# main.net
KiCad netlist of a schematic drawn in EAGLE
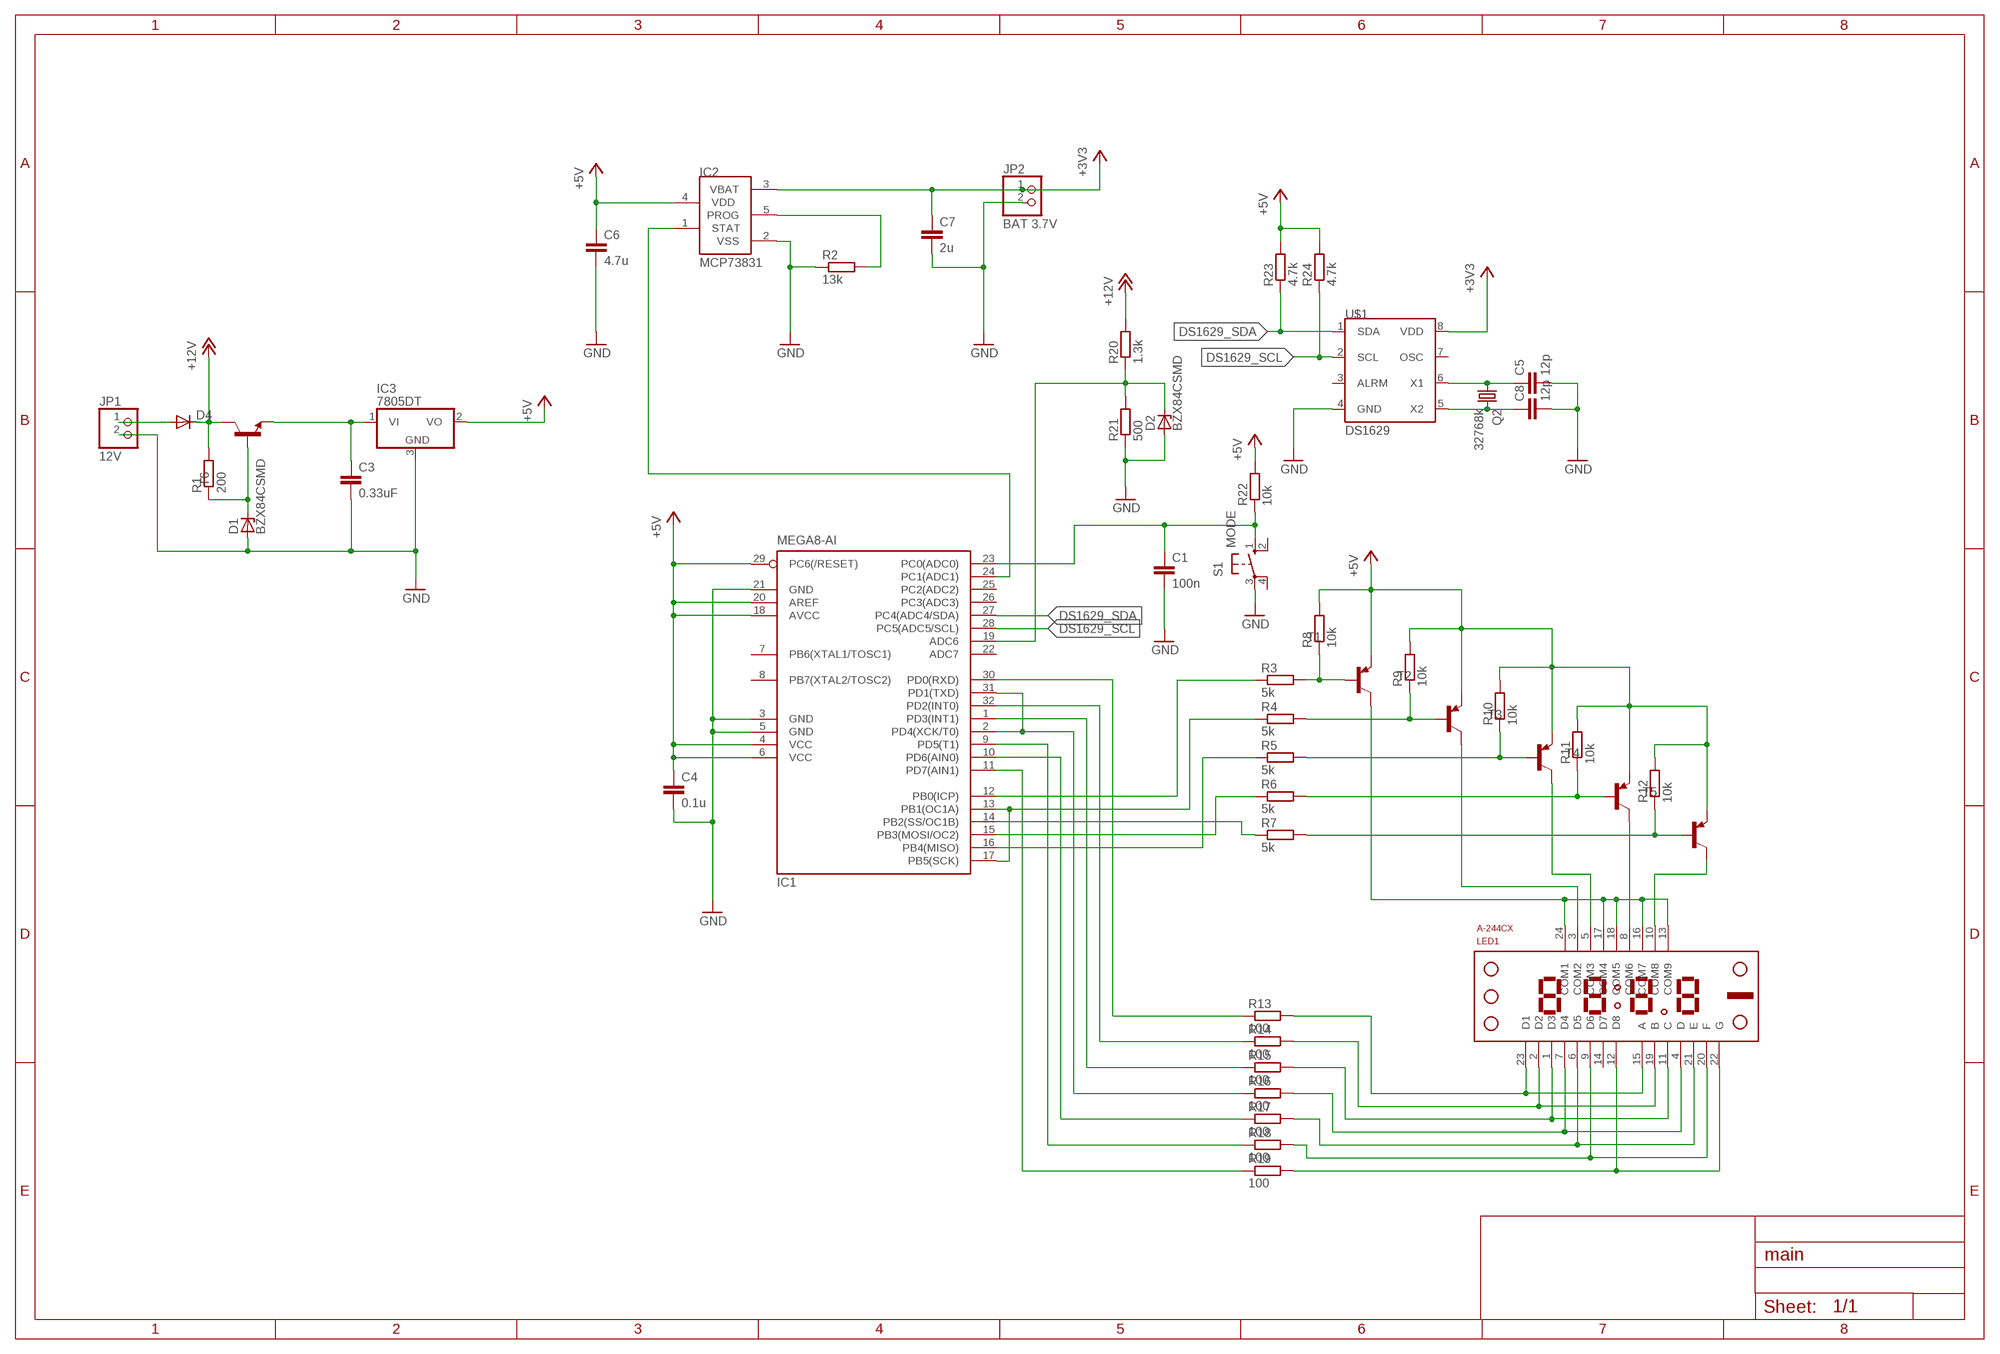
[diagram p0: schematic, sheet 1]

(export (version "E")
  (design (tool "Eeschema 10.0.6"))
  (components
    (comp (ref "C1")
      (value "100n")
      (footprint "eagle-import:C0805")
      (libsource (lib "eagle-import") (part "C-EUC0805"))
    )
    (comp (ref "C3")
      (value "0.33uF")
      (footprint "eagle-import:C1206")
      (libsource (lib "eagle-import") (part "C-EUC1206"))
    )
    (comp (ref "C4")
      (value "0.1u")
      (footprint "eagle-import:C0805")
      (libsource (lib "eagle-import") (part "C-EUC0805"))
    )
    (comp (ref "C5")
      (value "12p")
      (footprint "eagle-import:C0805")
      (libsource (lib "eagle-import") (part "C-EUC0805"))
    )
    (comp (ref "C6")
      (value "4.7u")
      (footprint "eagle-import:C1206")
      (libsource (lib "eagle-import") (part "C-EUC1206"))
    )
    (comp (ref "C7")
      (value "2u")
      (footprint "eagle-import:C1206")
      (libsource (lib "eagle-import") (part "C-EUC1206"))
    )
    (comp (ref "C8")
      (value "12p")
      (footprint "eagle-import:C0805")
      (libsource (lib "eagle-import") (part "C-EUC0805"))
    )
    (comp (ref "D1")
      (value "BZX84CSMD")
      (footprint "eagle-import:TO236")
      (libsource (lib "eagle-import") (part "BZX84CSMD"))
    )
    (comp (ref "D2")
      (value "BZX84CSMD")
      (footprint "eagle-import:TO236")
      (libsource (lib "eagle-import") (part "BZX84CSMD"))
    )
    (comp (ref "D4")
      (value "DIODE-D-7.5")
      (footprint "eagle-import:D-7.5")
      (libsource (lib "eagle-import") (part "DIODE-D-7.5"))
    )
    (comp (ref "IC1")
      (value "MEGA8-AI")
      (footprint "eagle-import:TQFP32-08")
      (fields (field (name "MPN") "ATMEGA8-16AU"))
      (libsource (lib "eagle-import") (part "MEGA8-AI"))
    )
    (comp (ref "IC2")
      (value "MCP73831")
      (footprint "eagle-import:SOT23-5L")
      (libsource (lib "eagle-import") (part "MCP73831"))
    )
    (comp (ref "IC3")
      (value "7805DT")
      (footprint "eagle-import:TO252")
      (libsource (lib "eagle-import") (part "78DT05"))
    )
    (comp (ref "JP1")
      (value "12V")
      (footprint "eagle-import:1X02")
      (libsource (lib "eagle-import") (part "PINHD-1X2"))
    )
    (comp (ref "JP2")
      (value "BAT 3.7V")
      (footprint "eagle-import:1X02")
      (libsource (lib "eagle-import") (part "PINHD-1X2"))
    )
    (comp (ref "LED1")
      (value "A-244CX")
      (footprint "eagle-import:C_A-244CX")
      (libsource (lib "eagle-import") (part "A-244CX"))
    )
    (comp (ref "Q2")
      (value "32768k")
      (footprint "eagle-import:TC26H")
      (libsource (lib "eagle-import") (part "CRYSTALTC26H"))
    )
    (comp (ref "R1")
      (value "200")
      (footprint "eagle-import:M0805")
      (libsource (lib "eagle-import") (part "R-EU_M0805"))
    )
    (comp (ref "R2")
      (value "13k")
      (footprint "eagle-import:M0805")
      (libsource (lib "eagle-import") (part "R-EU_M0805"))
    )
    (comp (ref "R3")
      (value "5k")
      (footprint "eagle-import:M0805")
      (libsource (lib "eagle-import") (part "R-EU_M0805"))
    )
    (comp (ref "R4")
      (value "5k")
      (footprint "eagle-import:M0805")
      (libsource (lib "eagle-import") (part "R-EU_M0805"))
    )
    (comp (ref "R5")
      (value "5k")
      (footprint "eagle-import:M0805")
      (libsource (lib "eagle-import") (part "R-EU_M0805"))
    )
    (comp (ref "R6")
      (value "5k")
      (footprint "eagle-import:M0805")
      (libsource (lib "eagle-import") (part "R-EU_M0805"))
    )
    (comp (ref "R7")
      (value "5k")
      (footprint "eagle-import:M0805")
      (libsource (lib "eagle-import") (part "R-EU_M0805"))
    )
    (comp (ref "R8")
      (value "10k")
      (footprint "eagle-import:M0805")
      (libsource (lib "eagle-import") (part "R-EU_M0805"))
    )
    (comp (ref "R9")
      (value "10k")
      (footprint "eagle-import:M0805")
      (libsource (lib "eagle-import") (part "R-EU_M0805"))
    )
    (comp (ref "R10")
      (value "10k")
      (footprint "eagle-import:M0805")
      (libsource (lib "eagle-import") (part "R-EU_M0805"))
    )
    (comp (ref "R11")
      (value "10k")
      (footprint "eagle-import:M0805")
      (libsource (lib "eagle-import") (part "R-EU_M0805"))
    )
    (comp (ref "R12")
      (value "10k")
      (footprint "eagle-import:M0805")
      (libsource (lib "eagle-import") (part "R-EU_M0805"))
    )
    (comp (ref "R13")
      (value "100")
      (footprint "eagle-import:M0805")
      (libsource (lib "eagle-import") (part "R-EU_M0805"))
    )
    (comp (ref "R14")
      (value "100")
      (footprint "eagle-import:M0805")
      (libsource (lib "eagle-import") (part "R-EU_M0805"))
    )
    (comp (ref "R15")
      (value "100")
      (footprint "eagle-import:M0805")
      (libsource (lib "eagle-import") (part "R-EU_M0805"))
    )
    (comp (ref "R16")
      (value "100")
      (footprint "eagle-import:M0805")
      (libsource (lib "eagle-import") (part "R-EU_M0805"))
    )
    (comp (ref "R17")
      (value "100")
      (footprint "eagle-import:M0805")
      (libsource (lib "eagle-import") (part "R-EU_M0805"))
    )
    (comp (ref "R18")
      (value "100")
      (footprint "eagle-import:M0805")
      (libsource (lib "eagle-import") (part "R-EU_M0805"))
    )
    (comp (ref "R19")
      (value "100")
      (footprint "eagle-import:M0805")
      (libsource (lib "eagle-import") (part "R-EU_M0805"))
    )
    (comp (ref "R20")
      (value "1.3k")
      (footprint "eagle-import:M0805")
      (libsource (lib "eagle-import") (part "R-EU_M0805"))
    )
    (comp (ref "R21")
      (value "500")
      (footprint "eagle-import:M0805")
      (libsource (lib "eagle-import") (part "R-EU_M0805"))
    )
    (comp (ref "R22")
      (value "10k")
      (footprint "eagle-import:M0805")
      (libsource (lib "eagle-import") (part "R-EU_M0805"))
    )
    (comp (ref "R23")
      (value "4.7k")
      (footprint "eagle-import:M0805")
      (libsource (lib "eagle-import") (part "R-EU_M0805"))
    )
    (comp (ref "R24")
      (value "4.7k")
      (footprint "eagle-import:M0805")
      (libsource (lib "eagle-import") (part "R-EU_M0805"))
    )
    (comp (ref "S1")
      (value "MODE")
      (footprint "eagle-import:B3F-10XX")
      (fields (field (name "MPN") "B3F-1000"))
      (libsource (lib "eagle-import") (part "10-XX"))
    )
    (comp (ref "T1")
      (value "BC807-25-PNP-SOT23-BEC")
      (footprint "eagle-import:SOT23-BEC")
      (libsource (lib "eagle-import") (part "-PNP-SOT23-BECBC807-25"))
    )
    (comp (ref "T2")
      (value "BC807-25-PNP-SOT23-BEC")
      (footprint "eagle-import:SOT23-BEC")
      (libsource (lib "eagle-import") (part "-PNP-SOT23-BECBC807-25"))
    )
    (comp (ref "T3")
      (value "BC807-25-PNP-SOT23-BEC")
      (footprint "eagle-import:SOT23-BEC")
      (libsource (lib "eagle-import") (part "-PNP-SOT23-BECBC807-25"))
    )
    (comp (ref "T4")
      (value "BC807-25-PNP-SOT23-BEC")
      (footprint "eagle-import:SOT23-BEC")
      (libsource (lib "eagle-import") (part "-PNP-SOT23-BECBC807-25"))
    )
    (comp (ref "T5")
      (value "BC807-25-PNP-SOT23-BEC")
      (footprint "eagle-import:SOT23-BEC")
      (libsource (lib "eagle-import") (part "-PNP-SOT23-BECBC807-25"))
    )
    (comp (ref "T6")
      (value "-NPN-SOT23-EBC")
      (footprint "eagle-import:SOT23-EBC")
      (libsource (lib "eagle-import") (part "-NPN-SOT23-EBC"))
    )
    (comp (ref "U$1")
      (value "DS1629")
      (footprint "eagle-import:SOIC-8")
      (libsource (lib "eagle-import") (part "DS1629"))
    )
  )
  (nets
    (net (code "1") (name "+3V3") (class "Default")
      (node (ref "C7") (pin "1") (pinfunction "1_1") (pintype "passive"))
      (node (ref "IC2") (pin "3") (pinfunction "VBAT_3") (pintype "bidirectional"))
      (node (ref "JP2") (pin "1") (pinfunction "1_1") (pintype "passive"))
      (node (ref "U$1") (pin "8") (pinfunction "VDD_8") (pintype "power_in"))
    )
    (net (code "2") (name "+5V") (class "Default")
      (node (ref "C4") (pin "1") (pinfunction "1_1") (pintype "passive"))
      (node (ref "C6") (pin "1") (pinfunction "1_1") (pintype "passive"))
      (node (ref "IC1") (pin "18") (pinfunction "AVCC_18") (pintype "power_in"))
      (node (ref "IC1") (pin "20") (pinfunction "AREF_20") (pintype "passive"))
      (node (ref "IC1") (pin "29") (pinfunction "PC6(/RESET)_29") (pintype "bidirectional"))
      (node (ref "IC1") (pin "4") (pinfunction "VCC_4") (pintype "power_in"))
      (node (ref "IC1") (pin "6") (pinfunction "VCC_6") (pintype "power_in"))
      (node (ref "IC2") (pin "4") (pinfunction "VDD_4") (pintype "bidirectional"))
      (node (ref "IC3") (pin "2") (pinfunction "VO_2") (pintype "passive"))
      (node (ref "R10") (pin "2") (pinfunction "2_2") (pintype "passive"))
      (node (ref "R11") (pin "2") (pinfunction "2_2") (pintype "passive"))
      (node (ref "R12") (pin "2") (pinfunction "2_2") (pintype "passive"))
      (node (ref "R22") (pin "2") (pinfunction "2_2") (pintype "passive"))
      (node (ref "R23") (pin "2") (pinfunction "2_2") (pintype "passive"))
      (node (ref "R24") (pin "2") (pinfunction "2_2") (pintype "passive"))
      (node (ref "R8") (pin "2") (pinfunction "2_2") (pintype "passive"))
      (node (ref "R9") (pin "2") (pinfunction "2_2") (pintype "passive"))
      (node (ref "T1") (pin "E") (pinfunction "E_E") (pintype "passive"))
      (node (ref "T2") (pin "E") (pinfunction "E_E") (pintype "passive"))
      (node (ref "T3") (pin "E") (pinfunction "E_E") (pintype "passive"))
      (node (ref "T4") (pin "E") (pinfunction "E_E") (pintype "passive"))
      (node (ref "T5") (pin "E") (pinfunction "E_E") (pintype "passive"))
    )
    (net (code "3") (name "+12V") (class "Default")
      (node (ref "D4") (pin "C") (pinfunction "C_C") (pintype "passive"))
      (node (ref "R1") (pin "2") (pinfunction "2_2") (pintype "passive"))
      (node (ref "R20") (pin "2") (pinfunction "2_2") (pintype "passive"))
      (node (ref "T6") (pin "C") (pinfunction "C_C") (pintype "passive"))
    )
    (net (code "4") (name "DS1629_SCL") (class "Default")
      (node (ref "IC1") (pin "28") (pinfunction "PC5(ADC5/SCL)_28") (pintype "bidirectional"))
      (node (ref "R24") (pin "1") (pinfunction "1_1") (pintype "passive"))
      (node (ref "U$1") (pin "2") (pinfunction "SCL_2") (pintype "input"))
    )
    (net (code "5") (name "DS1629_SDA") (class "Default")
      (node (ref "IC1") (pin "27") (pinfunction "PC4(ADC4/SDA)_27") (pintype "bidirectional"))
      (node (ref "R23") (pin "1") (pinfunction "1_1") (pintype "passive"))
      (node (ref "U$1") (pin "1") (pinfunction "SDA_1") (pintype "bidirectional"))
    )
    (net (code "6") (name "GND") (class "Default")
      (node (ref "C1") (pin "2") (pinfunction "2_2") (pintype "passive"))
      (node (ref "C3") (pin "2") (pinfunction "2_2") (pintype "passive"))
      (node (ref "C4") (pin "2") (pinfunction "2_2") (pintype "passive"))
      (node (ref "C5") (pin "2") (pinfunction "2_2") (pintype "passive"))
      (node (ref "C6") (pin "2") (pinfunction "2_2") (pintype "passive"))
      (node (ref "C7") (pin "2") (pinfunction "2_2") (pintype "passive"))
      (node (ref "C8") (pin "2") (pinfunction "2_2") (pintype "passive"))
      (node (ref "D1") (pin "A") (pinfunction "A_A") (pintype "passive"))
      (node (ref "D2") (pin "A") (pinfunction "A_A") (pintype "passive"))
      (node (ref "IC1") (pin "21") (pinfunction "GND_21") (pintype "power_in"))
      (node (ref "IC1") (pin "3") (pinfunction "GND_3") (pintype "power_in"))
      (node (ref "IC1") (pin "5") (pinfunction "GND_5") (pintype "power_in"))
      (node (ref "IC2") (pin "2") (pinfunction "VSS_2") (pintype "bidirectional"))
      (node (ref "IC3") (pin "3") (pinfunction "GND_3") (pintype "passive"))
      (node (ref "JP1") (pin "2") (pinfunction "2_2") (pintype "passive"))
      (node (ref "JP2") (pin "2") (pinfunction "2_2") (pintype "passive"))
      (node (ref "R2") (pin "1") (pinfunction "1_1") (pintype "passive"))
      (node (ref "R21") (pin "1") (pinfunction "1_1") (pintype "passive"))
      (node (ref "S1") (pin "3") (pinfunction "P_3") (pintype "passive"))
      (node (ref "U$1") (pin "4") (pinfunction "GND_4") (pintype "power_in"))
    )
    (net (code "7") (name "Net-(D1-PadC)") (class "Default")
      (node (ref "D1") (pin "C") (pinfunction "C_C") (pintype "passive"))
      (node (ref "R1") (pin "1") (pinfunction "1_1") (pintype "passive"))
      (node (ref "T6") (pin "B") (pinfunction "B_B") (pintype "passive"))
    )
    (net (code "8") (name "Net-(D4-PadA)") (class "Default")
      (node (ref "D4") (pin "A") (pinfunction "A_A") (pintype "passive"))
      (node (ref "JP1") (pin "1") (pinfunction "1_1") (pintype "passive"))
    )
    (net (code "9") (name "Net-(IC1-ADC6)") (class "Default")
      (node (ref "D2") (pin "C") (pinfunction "C_C") (pintype "passive"))
      (node (ref "IC1") (pin "19") (pinfunction "ADC6_19") (pintype "bidirectional"))
      (node (ref "R20") (pin "1") (pinfunction "1_1") (pintype "passive"))
      (node (ref "R21") (pin "2") (pinfunction "2_2") (pintype "passive"))
    )
    (net (code "10") (name "Net-(IC1-PB0(ICP))") (class "Default")
      (node (ref "IC1") (pin "12") (pinfunction "PB0(ICP)_12") (pintype "bidirectional"))
      (node (ref "R3") (pin "1") (pinfunction "1_1") (pintype "passive"))
    )
    (net (code "11") (name "Net-(IC1-PB1(OC1A))") (class "Default")
      (node (ref "IC1") (pin "13") (pinfunction "PB1(OC1A)_13") (pintype "bidirectional"))
      (node (ref "IC1") (pin "17") (pinfunction "PB5(SCK)_17") (pintype "bidirectional"))
      (node (ref "R4") (pin "1") (pinfunction "1_1") (pintype "passive"))
    )
    (net (code "12") (name "Net-(IC1-PB2(SS{slash}OC1B))") (class "Default")
      (node (ref "IC1") (pin "14") (pinfunction "PB2(SS/OC1B)_14") (pintype "bidirectional"))
      (node (ref "R7") (pin "1") (pinfunction "1_1") (pintype "passive"))
    )
    (net (code "13") (name "Net-(IC1-PB3(MOSI{slash}OC2))") (class "Default")
      (node (ref "IC1") (pin "15") (pinfunction "PB3(MOSI/OC2)_15") (pintype "bidirectional"))
      (node (ref "R6") (pin "1") (pinfunction "1_1") (pintype "passive"))
    )
    (net (code "14") (name "Net-(IC1-PB4(MISO))") (class "Default")
      (node (ref "IC1") (pin "16") (pinfunction "PB4(MISO)_16") (pintype "bidirectional"))
      (node (ref "R5") (pin "1") (pinfunction "1_1") (pintype "passive"))
    )
    (net (code "15") (name "Net-(IC1-PC0(ADC0))") (class "Default")
      (node (ref "C1") (pin "1") (pinfunction "1_1") (pintype "passive"))
      (node (ref "IC1") (pin "23") (pinfunction "PC0(ADC0)_23") (pintype "bidirectional"))
      (node (ref "R22") (pin "1") (pinfunction "1_1") (pintype "passive"))
      (node (ref "S1") (pin "1") (pinfunction "S_1") (pintype "passive"))
    )
    (net (code "16") (name "Net-(IC1-PC1(ADC1))") (class "Default")
      (node (ref "IC1") (pin "24") (pinfunction "PC1(ADC1)_24") (pintype "bidirectional"))
      (node (ref "IC2") (pin "1") (pinfunction "STAT_1") (pintype "bidirectional"))
    )
    (net (code "17") (name "Net-(IC1-PD0(RXD))") (class "Default")
      (node (ref "IC1") (pin "30") (pinfunction "PD0(RXD)_30") (pintype "bidirectional"))
      (node (ref "R13") (pin "1") (pinfunction "1_1") (pintype "passive"))
    )
    (net (code "18") (name "Net-(IC1-PD1(TXD))") (class "Default")
      (node (ref "IC1") (pin "2") (pinfunction "PD4(XCK/T0)_2") (pintype "bidirectional"))
      (node (ref "IC1") (pin "31") (pinfunction "PD1(TXD)_31") (pintype "bidirectional"))
      (node (ref "R16") (pin "1") (pinfunction "1_1") (pintype "passive"))
    )
    (net (code "19") (name "Net-(IC1-PD2(INT0))") (class "Default")
      (node (ref "IC1") (pin "32") (pinfunction "PD2(INT0)_32") (pintype "bidirectional"))
      (node (ref "R14") (pin "1") (pinfunction "1_1") (pintype "passive"))
    )
    (net (code "20") (name "Net-(IC1-PD3(INT1))") (class "Default")
      (node (ref "IC1") (pin "1") (pinfunction "PD3(INT1)_1") (pintype "bidirectional"))
      (node (ref "R15") (pin "1") (pinfunction "1_1") (pintype "passive"))
    )
    (net (code "21") (name "Net-(IC1-PD5(T1))") (class "Default")
      (node (ref "IC1") (pin "9") (pinfunction "PD5(T1)_9") (pintype "bidirectional"))
      (node (ref "R18") (pin "1") (pinfunction "1_1") (pintype "passive"))
    )
    (net (code "22") (name "Net-(IC1-PD6(AIN0))") (class "Default")
      (node (ref "IC1") (pin "10") (pinfunction "PD6(AIN0)_10") (pintype "bidirectional"))
      (node (ref "R17") (pin "1") (pinfunction "1_1") (pintype "passive"))
    )
    (net (code "23") (name "Net-(IC1-PD7(AIN1))") (class "Default")
      (node (ref "IC1") (pin "11") (pinfunction "PD7(AIN1)_11") (pintype "bidirectional"))
      (node (ref "R19") (pin "1") (pinfunction "1_1") (pintype "passive"))
    )
    (net (code "24") (name "Net-(IC2-PROG)") (class "Default")
      (node (ref "IC2") (pin "5") (pinfunction "PROG_5") (pintype "bidirectional"))
      (node (ref "R2") (pin "2") (pinfunction "2_2") (pintype "passive"))
    )
    (net (code "25") (name "Net-(IC3-VI)") (class "Default")
      (node (ref "C3") (pin "1") (pinfunction "1_1") (pintype "passive"))
      (node (ref "IC3") (pin "1") (pinfunction "VI_1") (pintype "input"))
      (node (ref "T6") (pin "E") (pinfunction "E_E") (pintype "passive"))
    )
    (net (code "26") (name "Net-(LED1-A)") (class "Default")
      (node (ref "LED1") (pin "15") (pinfunction "A_15") (pintype "bidirectional"))
      (node (ref "LED1") (pin "23") (pinfunction "D1_23") (pintype "bidirectional"))
      (node (ref "R13") (pin "2") (pinfunction "2_2") (pintype "passive"))
    )
    (net (code "27") (name "Net-(LED1-B)") (class "Default")
      (node (ref "LED1") (pin "19") (pinfunction "B_19") (pintype "bidirectional"))
      (node (ref "LED1") (pin "2") (pinfunction "D2_2") (pintype "bidirectional"))
      (node (ref "R14") (pin "2") (pinfunction "2_2") (pintype "passive"))
    )
    (net (code "28") (name "Net-(LED1-C)") (class "Default")
      (node (ref "LED1") (pin "1") (pinfunction "D3_1") (pintype "bidirectional"))
      (node (ref "LED1") (pin "11") (pinfunction "C_11") (pintype "bidirectional"))
      (node (ref "R15") (pin "2") (pinfunction "2_2") (pintype "passive"))
    )
    (net (code "29") (name "Net-(LED1-COM1)") (class "Default")
      (node (ref "LED1") (pin "13") (pinfunction "COM9_13") (pintype "bidirectional"))
      (node (ref "LED1") (pin "16") (pinfunction "COM7_16") (pintype "bidirectional"))
      (node (ref "LED1") (pin "17") (pinfunction "COM4_17") (pintype "bidirectional"))
      (node (ref "LED1") (pin "18") (pinfunction "COM5_18") (pintype "bidirectional"))
      (node (ref "LED1") (pin "24") (pinfunction "COM1_24") (pintype "bidirectional"))
      (node (ref "T1") (pin "C") (pinfunction "C_C") (pintype "passive"))
    )
    (net (code "30") (name "Net-(LED1-COM2)") (class "Default")
      (node (ref "LED1") (pin "3") (pinfunction "COM2_3") (pintype "bidirectional"))
      (node (ref "T2") (pin "C") (pinfunction "C_C") (pintype "passive"))
    )
    (net (code "31") (name "Net-(LED1-COM3)") (class "Default")
      (node (ref "LED1") (pin "5") (pinfunction "COM3_5") (pintype "bidirectional"))
      (node (ref "T3") (pin "C") (pinfunction "C_C") (pintype "passive"))
    )
    (net (code "32") (name "Net-(LED1-COM6)") (class "Default")
      (node (ref "LED1") (pin "8") (pinfunction "COM6_8") (pintype "bidirectional"))
      (node (ref "T4") (pin "C") (pinfunction "C_C") (pintype "passive"))
    )
    (net (code "33") (name "Net-(LED1-COM8)") (class "Default")
      (node (ref "LED1") (pin "10") (pinfunction "COM8_10") (pintype "bidirectional"))
      (node (ref "T5") (pin "C") (pinfunction "C_C") (pintype "passive"))
    )
    (net (code "34") (name "Net-(LED1-D)") (class "Default")
      (node (ref "LED1") (pin "4") (pinfunction "D_4") (pintype "bidirectional"))
      (node (ref "LED1") (pin "7") (pinfunction "D4_7") (pintype "bidirectional"))
      (node (ref "R16") (pin "2") (pinfunction "2_2") (pintype "passive"))
    )
    (net (code "35") (name "Net-(LED1-D5)") (class "Default")
      (node (ref "LED1") (pin "21") (pinfunction "E_21") (pintype "bidirectional"))
      (node (ref "LED1") (pin "6") (pinfunction "D5_6") (pintype "bidirectional"))
      (node (ref "R17") (pin "2") (pinfunction "2_2") (pintype "passive"))
    )
    (net (code "36") (name "Net-(LED1-D6)") (class "Default")
      (node (ref "LED1") (pin "20") (pinfunction "F_20") (pintype "bidirectional"))
      (node (ref "LED1") (pin "9") (pinfunction "D6_9") (pintype "bidirectional"))
      (node (ref "R18") (pin "2") (pinfunction "2_2") (pintype "passive"))
    )
    (net (code "37") (name "Net-(LED1-D8)") (class "Default")
      (node (ref "LED1") (pin "12") (pinfunction "D8_12") (pintype "bidirectional"))
      (node (ref "LED1") (pin "22") (pinfunction "G_22") (pintype "bidirectional"))
      (node (ref "R19") (pin "2") (pinfunction "2_2") (pintype "passive"))
    )
    (net (code "38") (name "Net-(R3-Pad2)") (class "Default")
      (node (ref "R3") (pin "2") (pinfunction "2_2") (pintype "passive"))
      (node (ref "R8") (pin "1") (pinfunction "1_1") (pintype "passive"))
      (node (ref "T1") (pin "B") (pinfunction "B_B") (pintype "passive"))
    )
    (net (code "39") (name "Net-(R4-Pad2)") (class "Default")
      (node (ref "R4") (pin "2") (pinfunction "2_2") (pintype "passive"))
      (node (ref "R9") (pin "1") (pinfunction "1_1") (pintype "passive"))
      (node (ref "T2") (pin "B") (pinfunction "B_B") (pintype "passive"))
    )
    (net (code "40") (name "Net-(R10-Pad1)") (class "Default")
      (node (ref "R10") (pin "1") (pinfunction "1_1") (pintype "passive"))
      (node (ref "R5") (pin "2") (pinfunction "2_2") (pintype "passive"))
      (node (ref "T3") (pin "B") (pinfunction "B_B") (pintype "passive"))
    )
    (net (code "41") (name "Net-(R11-Pad1)") (class "Default")
      (node (ref "R11") (pin "1") (pinfunction "1_1") (pintype "passive"))
      (node (ref "R6") (pin "2") (pinfunction "2_2") (pintype "passive"))
      (node (ref "T4") (pin "B") (pinfunction "B_B") (pintype "passive"))
    )
    (net (code "42") (name "Net-(R12-Pad1)") (class "Default")
      (node (ref "R12") (pin "1") (pinfunction "1_1") (pintype "passive"))
      (node (ref "R7") (pin "2") (pinfunction "2_2") (pintype "passive"))
      (node (ref "T5") (pin "B") (pinfunction "B_B") (pintype "passive"))
    )
    (net (code "43") (name "Net-(U$1-X1)") (class "Default")
      (node (ref "C5") (pin "1") (pinfunction "1_1") (pintype "passive"))
      (node (ref "Q2") (pin "1") (pinfunction "1_1") (pintype "passive"))
      (node (ref "U$1") (pin "6") (pinfunction "X1_6") (pintype "input"))
    )
    (net (code "44") (name "Net-(U$1-X2)") (class "Default")
      (node (ref "C8") (pin "1") (pinfunction "1_1") (pintype "passive"))
      (node (ref "Q2") (pin "2") (pinfunction "2_2") (pintype "passive"))
      (node (ref "U$1") (pin "5") (pinfunction "X2_5") (pintype "output"))
    )
    (net (code "45") (name "unconnected-(IC1-ADC7-Pad22)") (class "Default")
      (node (ref "IC1") (pin "22") (pinfunction "ADC7_22") (pintype "bidirectional"))
    )
    (net (code "46") (name "unconnected-(IC1-PB6(XTAL1{slash}TOSC1)-Pad7)") (class "Default")
      (node (ref "IC1") (pin "7") (pinfunction "PB6(XTAL1/TOSC1)_7") (pintype "bidirectional"))
    )
    (net (code "47") (name "unconnected-(IC1-PB7(XTAL2{slash}TOSC2)-Pad8)") (class "Default")
      (node (ref "IC1") (pin "8") (pinfunction "PB7(XTAL2/TOSC2)_8") (pintype "bidirectional"))
    )
    (net (code "48") (name "unconnected-(IC1-PC2(ADC2)-Pad25)") (class "Default")
      (node (ref "IC1") (pin "25") (pinfunction "PC2(ADC2)_25") (pintype "bidirectional"))
    )
    (net (code "49") (name "unconnected-(IC1-PC3(ADC3)-Pad26)") (class "Default")
      (node (ref "IC1") (pin "26") (pinfunction "PC3(ADC3)_26") (pintype "bidirectional"))
    )
    (net (code "50") (name "unconnected-(LED1-D7-Pad14)") (class "Default")
      (node (ref "LED1") (pin "14") (pinfunction "D7_14") (pintype "bidirectional"))
    )
    (net (code "51") (name "unconnected-(S1-P1-Pad4)") (class "Default")
      (node (ref "S1") (pin "4") (pinfunction "P1_4") (pintype "passive"))
    )
    (net (code "52") (name "unconnected-(S1-S1-Pad2)") (class "Default")
      (node (ref "S1") (pin "2") (pinfunction "S1_2") (pintype "passive"))
    )
    (net (code "53") (name "unconnected-(U$1-ALRM-Pad3)") (class "Default")
      (node (ref "U$1") (pin "3") (pinfunction "ALRM_3") (pintype "output"))
    )
    (net (code "54") (name "unconnected-(U$1-OSC-Pad7)") (class "Default")
      (node (ref "U$1") (pin "7") (pinfunction "OSC_7") (pintype "output"))
    )
  )
)
